# arduino_basic_example.net
KiCad netlist of a schematic drawn in EAGLE
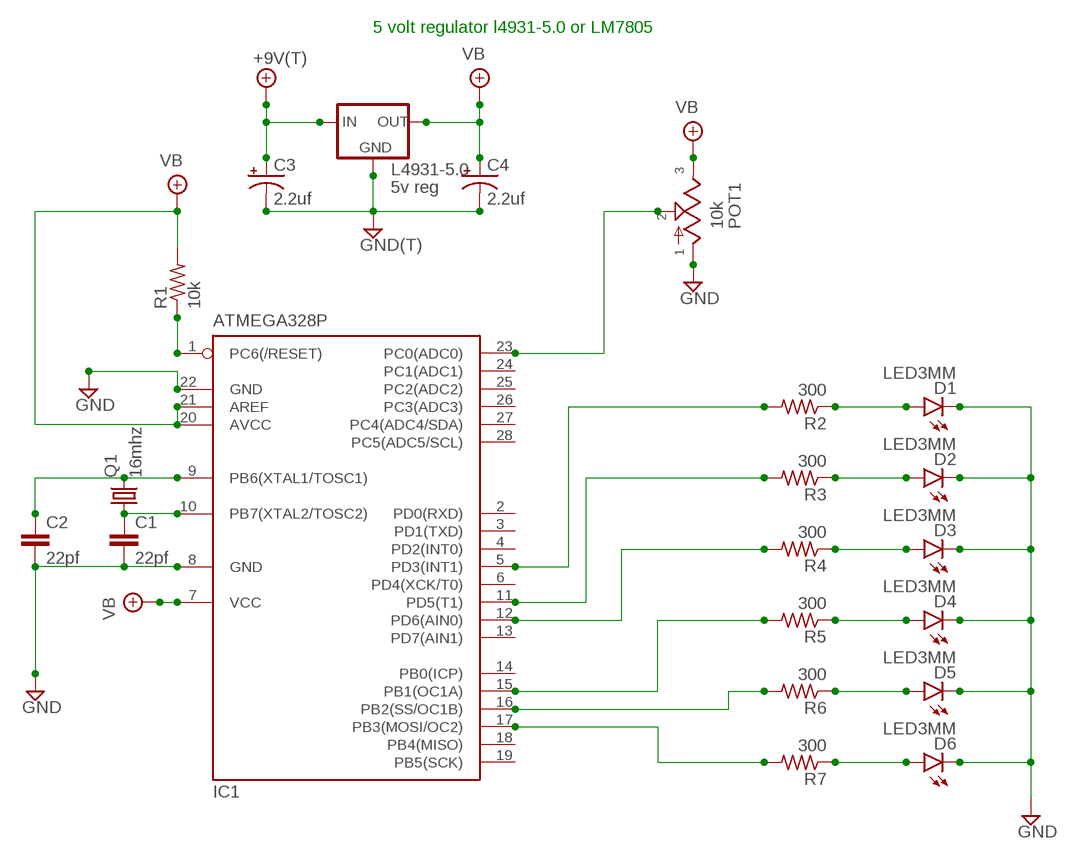
[diagram p0: schematic, sheet 1]

(export (version "E")
  (design (tool "Eeschema 10.0.6"))
  (components
    (comp (ref "+9V1")
      (value "+9V(T)")
      (footprint "eagle-import:SQUARE")
      (libsource (lib "eagle-import") (part "+9V(T)"))
    )
    (comp (ref "C1")
      (value "22pf")
      (footprint "eagle-import:050X030_025")
      (libsource (lib "eagle-import") (part "050X030_0251"))
    )
    (comp (ref "C2")
      (value "22pf")
      (footprint "eagle-import:050X030_025")
      (libsource (lib "eagle-import") (part "050X030_0251"))
    )
    (comp (ref "C3")
      (value "2.2uf")
      (footprint "eagle-import:050_020")
      (libsource (lib "eagle-import") (part "050"))
    )
    (comp (ref "C4")
      (value "2.2uf")
      (footprint "eagle-import:050_020")
      (libsource (lib "eagle-import") (part "050"))
    )
    (comp (ref "D1")
      (value "LED3MM")
      (footprint "eagle-import:LED3MM")
      (libsource (lib "eagle-import") (part "LED3MM"))
    )
    (comp (ref "D2")
      (value "LED3MM")
      (footprint "eagle-import:LED3MM")
      (libsource (lib "eagle-import") (part "LED3MM"))
    )
    (comp (ref "D3")
      (value "LED3MM")
      (footprint "eagle-import:LED3MM")
      (libsource (lib "eagle-import") (part "LED3MM"))
    )
    (comp (ref "D4")
      (value "LED3MM")
      (footprint "eagle-import:LED3MM")
      (libsource (lib "eagle-import") (part "LED3MM"))
    )
    (comp (ref "D5")
      (value "LED3MM")
      (footprint "eagle-import:LED3MM")
      (libsource (lib "eagle-import") (part "LED3MM"))
    )
    (comp (ref "D6")
      (value "LED3MM")
      (footprint "eagle-import:LED3MM")
      (libsource (lib "eagle-import") (part "LED3MM"))
    )
    (comp (ref "GND1")
      (value "GND(T)")
      (footprint "eagle-import:SQUARE")
      (libsource (lib "eagle-import") (part "GND(T)"))
    )
    (comp (ref "IC1")
      (value "ATMEGA328P")
      (footprint "eagle-import:DIL28-3")
      (libsource (lib "eagle-import") (part "MEGA8-P"))
    )
    (comp (ref "L4931-5.0")
      (value "5v reg")
      (footprint "eagle-import:78LXX")
      (libsource (lib "eagle-import") (part "78LXX"))
    )
    (comp (ref "POT1")
      (value "10k")
      (footprint "eagle-import:16MM")
      (libsource (lib "eagle-import") (part "POT16MM"))
    )
    (comp (ref "Q1")
      (value "16mhz")
      (footprint "eagle-import:HC49_S")
      (libsource (lib "eagle-import") (part "CRYSTALHC49S"))
    )
    (comp (ref "R1")
      (value "10k")
      (footprint "eagle-import:R0207_3")
      (libsource (lib "eagle-import") (part "6MM.3"))
    )
    (comp (ref "R2")
      (value "300")
      (footprint "eagle-import:R0207_3")
      (libsource (lib "eagle-import") (part "6MM.3"))
    )
    (comp (ref "R3")
      (value "300")
      (footprint "eagle-import:R0207_3")
      (libsource (lib "eagle-import") (part "6MM.3"))
    )
    (comp (ref "R4")
      (value "300")
      (footprint "eagle-import:R0207_3")
      (libsource (lib "eagle-import") (part "6MM.3"))
    )
    (comp (ref "R5")
      (value "300")
      (footprint "eagle-import:R0207_3")
      (libsource (lib "eagle-import") (part "6MM.3"))
    )
    (comp (ref "R6")
      (value "300")
      (footprint "eagle-import:R0207_3")
      (libsource (lib "eagle-import") (part "6MM.3"))
    )
    (comp (ref "R7")
      (value "300")
      (footprint "eagle-import:R0207_3")
      (libsource (lib "eagle-import") (part "6MM.3"))
    )
  )
  (nets
    (net (code "1") (name "+9V(T)") (class "Default")
      (node (ref "+9V1") (pin "1") (pinfunction "+9V_1") (pintype "power_in"))
      (node (ref "C3") (pin "+") (pinfunction "+_+") (pintype "passive"))
      (node (ref "L4931-5.0") (pin "IN") (pinfunction "IN_IN") (pintype "input"))
    )
    (net (code "2") (name "GND") (class "Default")
      (node (ref "C1") (pin "2") (pinfunction "2_2") (pintype "passive"))
      (node (ref "C2") (pin "2") (pinfunction "2_2") (pintype "passive"))
      (node (ref "C3") (pin "-") (pinfunction "-_-") (pintype "passive"))
      (node (ref "C4") (pin "-") (pinfunction "-_-") (pintype "passive"))
      (node (ref "D1") (pin "K") (pinfunction "C_K") (pintype "passive"))
      (node (ref "D2") (pin "K") (pinfunction "C_K") (pintype "passive"))
      (node (ref "D3") (pin "K") (pinfunction "C_K") (pintype "passive"))
      (node (ref "D4") (pin "K") (pinfunction "C_K") (pintype "passive"))
      (node (ref "D5") (pin "K") (pinfunction "C_K") (pintype "passive"))
      (node (ref "D6") (pin "K") (pinfunction "C_K") (pintype "passive"))
      (node (ref "GND1") (pin "1") (pinfunction "GND_1") (pintype "power_in"))
      (node (ref "IC1") (pin "22") (pinfunction "GND_22") (pintype "power_in"))
      (node (ref "IC1") (pin "8") (pinfunction "GND_8") (pintype "power_in"))
      (node (ref "L4931-5.0") (pin "GND") (pinfunction "GND_GND") (pintype "input"))
      (node (ref "POT1") (pin "1") (pinfunction "1_1") (pintype "passive"))
    )
    (net (code "3") (name "Net-(D1-PadA)") (class "Default")
      (node (ref "D1") (pin "A") (pinfunction "A_A") (pintype "passive"))
      (node (ref "R2") (pin "1") (pinfunction "1_1") (pintype "passive"))
    )
    (net (code "4") (name "Net-(D2-PadA)") (class "Default")
      (node (ref "D2") (pin "A") (pinfunction "A_A") (pintype "passive"))
      (node (ref "R3") (pin "1") (pinfunction "1_1") (pintype "passive"))
    )
    (net (code "5") (name "Net-(D3-PadA)") (class "Default")
      (node (ref "D3") (pin "A") (pinfunction "A_A") (pintype "passive"))
      (node (ref "R4") (pin "1") (pinfunction "1_1") (pintype "passive"))
    )
    (net (code "6") (name "Net-(D4-PadA)") (class "Default")
      (node (ref "D4") (pin "A") (pinfunction "A_A") (pintype "passive"))
      (node (ref "R5") (pin "1") (pinfunction "1_1") (pintype "passive"))
    )
    (net (code "7") (name "Net-(D5-PadA)") (class "Default")
      (node (ref "D5") (pin "A") (pinfunction "A_A") (pintype "passive"))
      (node (ref "R6") (pin "1") (pinfunction "1_1") (pintype "passive"))
    )
    (net (code "8") (name "Net-(D6-PadA)") (class "Default")
      (node (ref "D6") (pin "A") (pinfunction "A_A") (pintype "passive"))
      (node (ref "R7") (pin "1") (pinfunction "1_1") (pintype "passive"))
    )
    (net (code "9") (name "Net-(IC1-PB1(OC1A))") (class "Default")
      (node (ref "IC1") (pin "15") (pinfunction "PB1(OC1A)_15") (pintype "bidirectional"))
      (node (ref "R5") (pin "2") (pinfunction "2_2") (pintype "passive"))
    )
    (net (code "10") (name "Net-(IC1-PB2(SS{slash}OC1B))") (class "Default")
      (node (ref "IC1") (pin "16") (pinfunction "PB2(SS/OC1B)_16") (pintype "bidirectional"))
      (node (ref "R6") (pin "2") (pinfunction "2_2") (pintype "passive"))
    )
    (net (code "11") (name "Net-(IC1-PB3(MOSI{slash}OC2))") (class "Default")
      (node (ref "IC1") (pin "17") (pinfunction "PB3(MOSI/OC2)_17") (pintype "bidirectional"))
      (node (ref "R7") (pin "2") (pinfunction "2_2") (pintype "passive"))
    )
    (net (code "12") (name "Net-(IC1-PB6(XTAL1{slash}TOSC1))") (class "Default")
      (node (ref "C2") (pin "1") (pinfunction "1_1") (pintype "passive"))
      (node (ref "IC1") (pin "9") (pinfunction "PB6(XTAL1/TOSC1)_9") (pintype "bidirectional"))
      (node (ref "Q1") (pin "2") (pinfunction "2_2") (pintype "passive"))
    )
    (net (code "13") (name "Net-(IC1-PB7(XTAL2{slash}TOSC2))") (class "Default")
      (node (ref "C1") (pin "1") (pinfunction "1_1") (pintype "passive"))
      (node (ref "IC1") (pin "10") (pinfunction "PB7(XTAL2/TOSC2)_10") (pintype "bidirectional"))
      (node (ref "Q1") (pin "1") (pinfunction "1_1") (pintype "passive"))
    )
    (net (code "14") (name "Net-(IC1-PC0(ADC0))") (class "Default")
      (node (ref "IC1") (pin "23") (pinfunction "PC0(ADC0)_23") (pintype "bidirectional"))
      (node (ref "POT1") (pin "2") (pinfunction "2_2") (pintype "passive"))
    )
    (net (code "15") (name "Net-(IC1-PC6({slash}RESET))") (class "Default")
      (node (ref "IC1") (pin "1") (pinfunction "PC6(/RESET)_1") (pintype "bidirectional"))
      (node (ref "R1") (pin "1") (pinfunction "1_1") (pintype "passive"))
    )
    (net (code "16") (name "Net-(IC1-PD3(INT1))") (class "Default")
      (node (ref "IC1") (pin "5") (pinfunction "PD3(INT1)_5") (pintype "bidirectional"))
      (node (ref "R2") (pin "2") (pinfunction "2_2") (pintype "passive"))
    )
    (net (code "17") (name "Net-(IC1-PD5(T1))") (class "Default")
      (node (ref "IC1") (pin "11") (pinfunction "PD5(T1)_11") (pintype "bidirectional"))
      (node (ref "R3") (pin "2") (pinfunction "2_2") (pintype "passive"))
    )
    (net (code "18") (name "Net-(IC1-PD6(AIN0))") (class "Default")
      (node (ref "IC1") (pin "12") (pinfunction "PD6(AIN0)_12") (pintype "bidirectional"))
      (node (ref "R4") (pin "2") (pinfunction "2_2") (pintype "passive"))
    )
    (net (code "19") (name "VB") (class "Default")
      (node (ref "C4") (pin "+") (pinfunction "+_+") (pintype "passive"))
      (node (ref "IC1") (pin "20") (pinfunction "AVCC_20") (pintype "power_in"))
      (node (ref "IC1") (pin "21") (pinfunction "AREF_21") (pintype "passive"))
      (node (ref "IC1") (pin "7") (pinfunction "VCC_7") (pintype "power_in"))
      (node (ref "L4931-5.0") (pin "OUT") (pinfunction "OUT_OUT") (pintype "passive"))
      (node (ref "POT1") (pin "3") (pinfunction "3_3") (pintype "passive"))
      (node (ref "R1") (pin "2") (pinfunction "2_2") (pintype "passive"))
    )
    (net (code "20") (name "unconnected-(IC1-PB0(ICP)-Pad14)") (class "Default")
      (node (ref "IC1") (pin "14") (pinfunction "PB0(ICP)_14") (pintype "bidirectional"))
    )
    (net (code "21") (name "unconnected-(IC1-PB4(MISO)-Pad18)") (class "Default")
      (node (ref "IC1") (pin "18") (pinfunction "PB4(MISO)_18") (pintype "bidirectional"))
    )
    (net (code "22") (name "unconnected-(IC1-PB5(SCK)-Pad19)") (class "Default")
      (node (ref "IC1") (pin "19") (pinfunction "PB5(SCK)_19") (pintype "bidirectional"))
    )
    (net (code "23") (name "unconnected-(IC1-PC1(ADC1)-Pad24)") (class "Default")
      (node (ref "IC1") (pin "24") (pinfunction "PC1(ADC1)_24") (pintype "bidirectional"))
    )
    (net (code "24") (name "unconnected-(IC1-PC2(ADC2)-Pad25)") (class "Default")
      (node (ref "IC1") (pin "25") (pinfunction "PC2(ADC2)_25") (pintype "bidirectional"))
    )
    (net (code "25") (name "unconnected-(IC1-PC3(ADC3)-Pad26)") (class "Default")
      (node (ref "IC1") (pin "26") (pinfunction "PC3(ADC3)_26") (pintype "bidirectional"))
    )
    (net (code "26") (name "unconnected-(IC1-PC4(ADC4{slash}SDA)-Pad27)") (class "Default")
      (node (ref "IC1") (pin "27") (pinfunction "PC4(ADC4/SDA)_27") (pintype "bidirectional"))
    )
    (net (code "27") (name "unconnected-(IC1-PC5(ADC5{slash}SCL)-Pad28)") (class "Default")
      (node (ref "IC1") (pin "28") (pinfunction "PC5(ADC5/SCL)_28") (pintype "bidirectional"))
    )
    (net (code "28") (name "unconnected-(IC1-PD0(RXD)-Pad2)") (class "Default")
      (node (ref "IC1") (pin "2") (pinfunction "PD0(RXD)_2") (pintype "bidirectional"))
    )
    (net (code "29") (name "unconnected-(IC1-PD1(TXD)-Pad3)") (class "Default")
      (node (ref "IC1") (pin "3") (pinfunction "PD1(TXD)_3") (pintype "bidirectional"))
    )
    (net (code "30") (name "unconnected-(IC1-PD2(INT0)-Pad4)") (class "Default")
      (node (ref "IC1") (pin "4") (pinfunction "PD2(INT0)_4") (pintype "bidirectional"))
    )
    (net (code "31") (name "unconnected-(IC1-PD4(XCK{slash}T0)-Pad6)") (class "Default")
      (node (ref "IC1") (pin "6") (pinfunction "PD4(XCK/T0)_6") (pintype "bidirectional"))
    )
    (net (code "32") (name "unconnected-(IC1-PD7(AIN1)-Pad13)") (class "Default")
      (node (ref "IC1") (pin "13") (pinfunction "PD7(AIN1)_13") (pintype "bidirectional"))
    )
  )
)
